# mb2.net
KiCad netlist of a schematic drawn in EAGLE
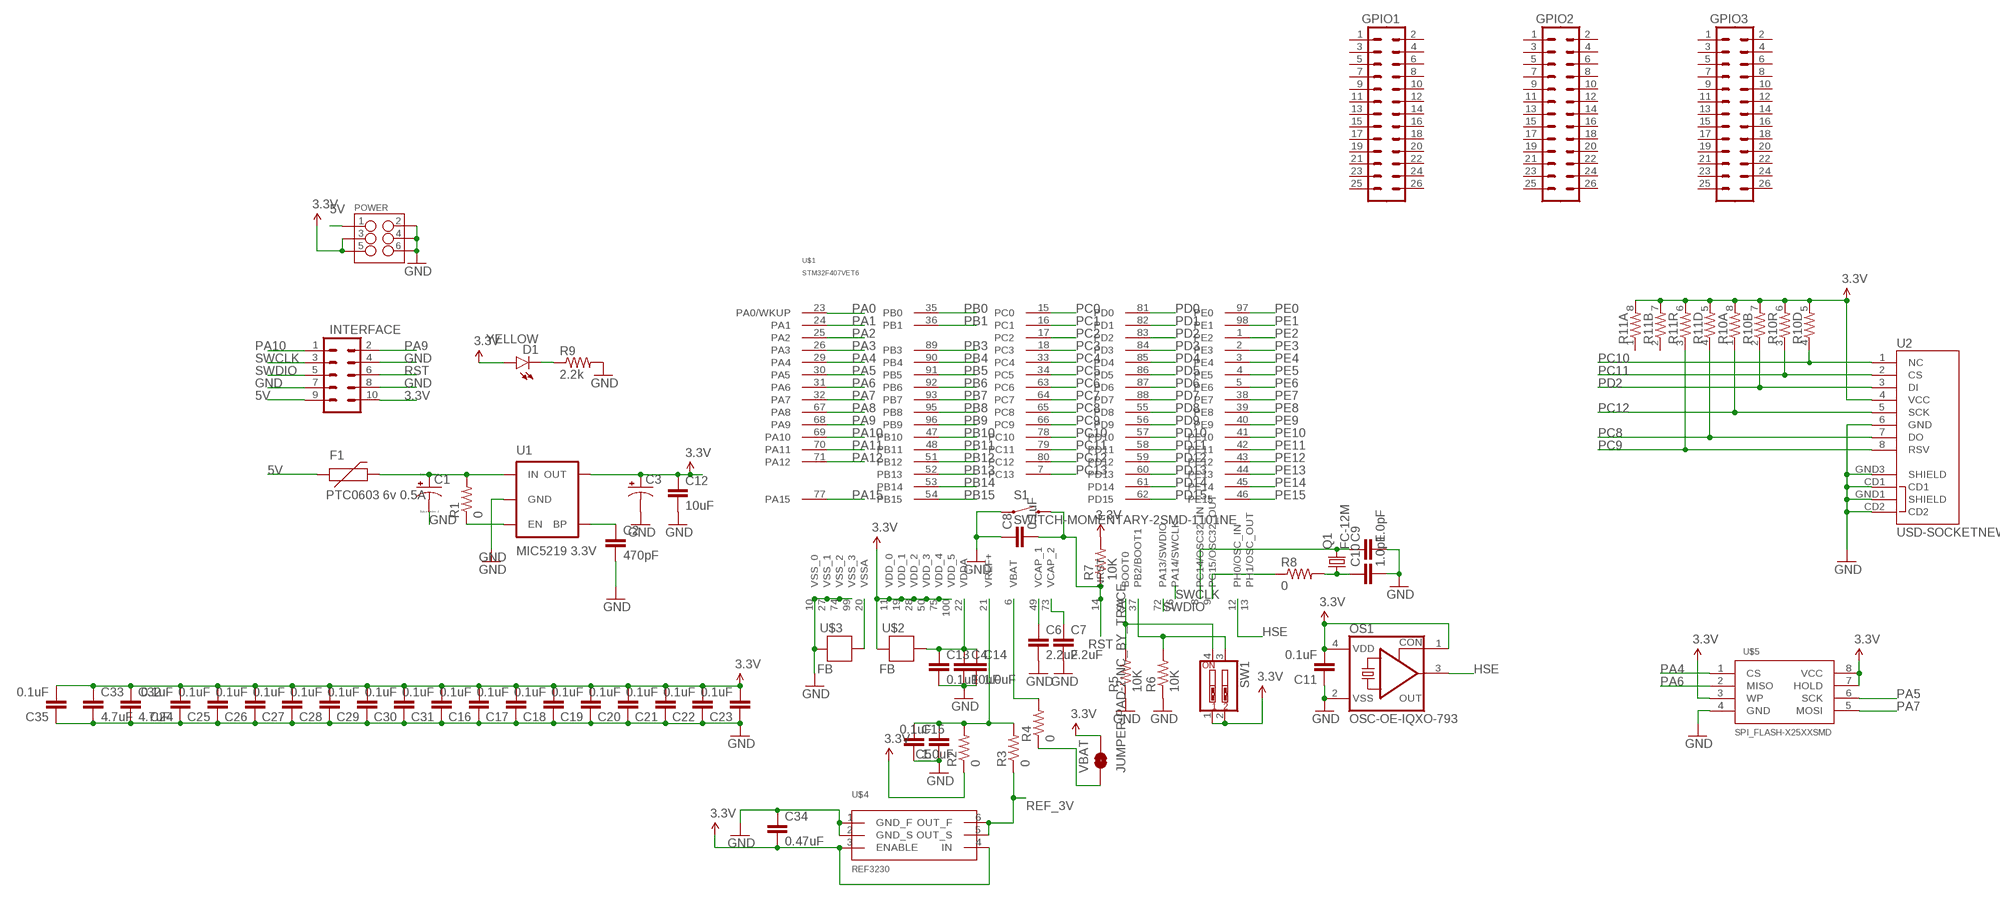
[diagram p0: schematic, sheet 1]

(export (version "E")
  (design (tool "Eeschema 10.0.6"))
  (components
    (comp (ref "C1")
      (value "CPOL-USB")
      (footprint "eagle-import:PANASONIC_B")
      (libsource (lib "eagle-import") (part "CPOL-USB"))
    )
    (comp (ref "C2")
      (value "470pF")
      (footprint "eagle-import:0603-CAP")
      (libsource (lib "eagle-import") (part "470PF-50V-5%(0603)SMD"))
    )
    (comp (ref "C3")
      (value "CAP_POL1206")
      (footprint "eagle-import:EIA3216")
      (libsource (lib "eagle-import") (part "CAP_POL1206"))
    )
    (comp (ref "C4")
      (value "10uF")
      (footprint "eagle-import:0603-CAP")
      (libsource (lib "eagle-import") (part "10UF-6.3V-20%(0603)"))
    )
    (comp (ref "C5")
      (value "0.1uF")
      (footprint "eagle-import:0603-CAP")
      (libsource (lib "eagle-import") (part "0.1UF-25V-5%(0603)"))
    )
    (comp (ref "C6")
      (value "2.2uF")
      (footprint "eagle-import:0603-CAP")
      (libsource (lib "eagle-import") (part "2.2UF-10V-20%(0603)"))
    )
    (comp (ref "C7")
      (value "2.2uF")
      (footprint "eagle-import:0603-CAP")
      (libsource (lib "eagle-import") (part "2.2UF-10V-20%(0603)"))
    )
    (comp (ref "C8")
      (value "0.1uF")
      (footprint "eagle-import:0603-CAP")
      (libsource (lib "eagle-import") (part "0.1UF-25V-5%(0603)"))
    )
    (comp (ref "C9")
      (value "1.0pF")
      (footprint "eagle-import:0603-CAP")
      (libsource (lib "eagle-import") (part "1.0PF-50V(-/+.25PF)(0603)"))
    )
    (comp (ref "C10")
      (value "1.0pF")
      (footprint "eagle-import:0603-CAP")
      (libsource (lib "eagle-import") (part "1.0PF-50V(-/+.25PF)(0603)"))
    )
    (comp (ref "C11")
      (value "0.1uF")
      (footprint "eagle-import:0603-CAP")
      (libsource (lib "eagle-import") (part "0.1UF-25V-5%(0603)"))
    )
    (comp (ref "C12")
      (value "10uF")
      (footprint "eagle-import:0603-CAP")
      (libsource (lib "eagle-import") (part "10UF-6.3V-20%(0603)"))
    )
    (comp (ref "C13")
      (value "0.1uF")
      (footprint "eagle-import:0603-CAP")
      (libsource (lib "eagle-import") (part "0.1UF-25V-5%(0603)"))
    )
    (comp (ref "C14")
      (value "1.0uF")
      (footprint "eagle-import:0603-CAP")
      (libsource (lib "eagle-import") (part "1.0UF-16V-10%(0603)"))
    )
    (comp (ref "C15")
      (value "1.0uF")
      (footprint "eagle-import:0603-CAP")
      (libsource (lib "eagle-import") (part "1.0UF-16V-10%(0603)"))
    )
    (comp (ref "C16")
      (value "0.1uF")
      (footprint "eagle-import:0603-CAP")
      (libsource (lib "eagle-import") (part "0.1UF-25V-5%(0603)"))
    )
    (comp (ref "C17")
      (value "0.1uF")
      (footprint "eagle-import:0603-CAP")
      (libsource (lib "eagle-import") (part "0.1UF-25V-5%(0603)"))
    )
    (comp (ref "C18")
      (value "0.1uF")
      (footprint "eagle-import:0603-CAP")
      (libsource (lib "eagle-import") (part "0.1UF-25V-5%(0603)"))
    )
    (comp (ref "C19")
      (value "0.1uF")
      (footprint "eagle-import:0603-CAP")
      (libsource (lib "eagle-import") (part "0.1UF-25V-5%(0603)"))
    )
    (comp (ref "C20")
      (value "0.1uF")
      (footprint "eagle-import:0603-CAP")
      (libsource (lib "eagle-import") (part "0.1UF-25V-5%(0603)"))
    )
    (comp (ref "C21")
      (value "0.1uF")
      (footprint "eagle-import:0603-CAP")
      (libsource (lib "eagle-import") (part "0.1UF-25V-5%(0603)"))
    )
    (comp (ref "C22")
      (value "0.1uF")
      (footprint "eagle-import:0603-CAP")
      (libsource (lib "eagle-import") (part "0.1UF-25V-5%(0603)"))
    )
    (comp (ref "C23")
      (value "0.1uF")
      (footprint "eagle-import:0603-CAP")
      (libsource (lib "eagle-import") (part "0.1UF-25V-5%(0603)"))
    )
    (comp (ref "C24")
      (value "0.1uF")
      (footprint "eagle-import:0603-CAP")
      (libsource (lib "eagle-import") (part "0.1UF-25V-5%(0603)"))
    )
    (comp (ref "C25")
      (value "0.1uF")
      (footprint "eagle-import:0603-CAP")
      (libsource (lib "eagle-import") (part "0.1UF-25V-5%(0603)"))
    )
    (comp (ref "C26")
      (value "0.1uF")
      (footprint "eagle-import:0603-CAP")
      (libsource (lib "eagle-import") (part "0.1UF-25V-5%(0603)"))
    )
    (comp (ref "C27")
      (value "0.1uF")
      (footprint "eagle-import:0603-CAP")
      (libsource (lib "eagle-import") (part "0.1UF-25V-5%(0603)"))
    )
    (comp (ref "C28")
      (value "0.1uF")
      (footprint "eagle-import:0603-CAP")
      (libsource (lib "eagle-import") (part "0.1UF-25V-5%(0603)"))
    )
    (comp (ref "C29")
      (value "0.1uF")
      (footprint "eagle-import:0603-CAP")
      (libsource (lib "eagle-import") (part "0.1UF-25V-5%(0603)"))
    )
    (comp (ref "C30")
      (value "0.1uF")
      (footprint "eagle-import:0603-CAP")
      (libsource (lib "eagle-import") (part "0.1UF-25V-5%(0603)"))
    )
    (comp (ref "C31")
      (value "0.1uF")
      (footprint "eagle-import:0603-CAP")
      (libsource (lib "eagle-import") (part "0.1UF-25V-5%(0603)"))
    )
    (comp (ref "C32")
      (value "4.7uF")
      (footprint "eagle-import:0603-CAP")
      (libsource (lib "eagle-import") (part "4.7UF-6.3V-10%(0603)0603"))
    )
    (comp (ref "C33")
      (value "4.7uF")
      (footprint "eagle-import:0603-CAP")
      (libsource (lib "eagle-import") (part "4.7UF-6.3V-10%(0603)0603"))
    )
    (comp (ref "C34")
      (value "0.47uF")
      (footprint "eagle-import:0603-CAP")
      (libsource (lib "eagle-import") (part "0.1UF-25V-5%(0603)"))
    )
    (comp (ref "C35")
      (value "0.1uF")
      (footprint "eagle-import:0603-CAP")
      (libsource (lib "eagle-import") (part "0.1UF-25V-5%(0603)"))
    )
    (comp (ref "D1")
      (value "YELLOW")
      (footprint "eagle-import:LED-1206")
      (libsource (lib "eagle-import") (part "LED-YELLOW1206"))
    )
    (comp (ref "F1")
      (value "PTC0603 6v 0.5A")
      (footprint "eagle-import:0603")
      (libsource (lib "eagle-import") (part "PTC0603"))
    )
    (comp (ref "GPIO1")
      (value "M13X22X13")
      (footprint "eagle-import:2X13")
      (libsource (lib "eagle-import") (part "M13X22X13"))
    )
    (comp (ref "GPIO2")
      (value "M13X22X13")
      (footprint "eagle-import:2X13")
      (libsource (lib "eagle-import") (part "M13X22X13"))
    )
    (comp (ref "GPIO3")
      (value "M13X22X13")
      (footprint "eagle-import:2X13")
      (libsource (lib "eagle-import") (part "M13X22X13"))
    )
    (comp (ref "INTERFACE")
      (value "M05X2RA")
      (footprint "eagle-import:2X5-RA")
      (libsource (lib "eagle-import") (part "M05X2RA"))
    )
    (comp (ref "OS1")
      (value "OSC-OE-IQXO-793")
      (footprint "eagle-import:2.5X2-4-PAD")
      (libsource (lib "eagle-import") (part "OSC-OE-IQXO-793"))
    )
    (comp (ref "POWER")
      (value "M03X22X3_SILK_MALE_PTH")
      (footprint "eagle-import:2X3")
      (libsource (lib "eagle-import") (part "M03X22X3_SILK_MALE_PTH"))
    )
    (comp (ref "Q1")
      (value "FC-12M")
      (footprint "eagle-import:FC-12M")
      (libsource (lib "eagle-import") (part "FC-12M"))
    )
    (comp (ref "R1")
      (value "0")
      (footprint "eagle-import:0603")
      (libsource (lib "eagle-import") (part "0OHM-1/10W-5%(0603)"))
    )
    (comp (ref "R2")
      (value "0")
      (footprint "eagle-import:0603")
      (libsource (lib "eagle-import") (part "0OHM-1/10W-5%(0603)"))
    )
    (comp (ref "R3")
      (value "0")
      (footprint "eagle-import:0603")
      (libsource (lib "eagle-import") (part "0OHM-1/10W-5%(0603)"))
    )
    (comp (ref "R4")
      (value "0")
      (footprint "eagle-import:0603")
      (libsource (lib "eagle-import") (part "0OHM-1/10W-5%(0603)"))
    )
    (comp (ref "R5")
      (value "10K")
      (footprint "eagle-import:0603-RES")
      (libsource (lib "eagle-import") (part "10KOHM-1/10W-1%(0603)0603"))
    )
    (comp (ref "R6")
      (value "10K")
      (footprint "eagle-import:0603-RES")
      (libsource (lib "eagle-import") (part "10KOHM-1/10W-1%(0603)0603"))
    )
    (comp (ref "R7")
      (value "10K")
      (footprint "eagle-import:0603-RES")
      (libsource (lib "eagle-import") (part "10KOHM-1/10W-1%(0603)0603"))
    )
    (comp (ref "R8")
      (value "0")
      (footprint "eagle-import:0603")
      (libsource (lib "eagle-import") (part "0OHM-1/10W-5%(0603)"))
    )
    (comp (ref "R9")
      (value "2.2k")
      (footprint "eagle-import:0603-RES")
      (libsource (lib "eagle-import") (part "2.2KOHM-1/10W-1%(0603)"))
    )
    (comp (ref "R10")
      (value "RESISTOR-ARRAY0603-ARV")
      (footprint "eagle-import:0603-ARV")
      (libsource (lib "eagle-import") (part "RESISTOR-ARRAY0603-ARV"))
    )
    (comp (ref "R11")
      (value "RESISTOR-ARRAY0603-ARV")
      (footprint "eagle-import:0603-ARV")
      (libsource (lib "eagle-import") (part "RESISTOR-ARRAY0603-ARV"))
    )
    (comp (ref "S1")
      (value "SWITCH-MOMENTARY-2SMD-1101NE")
      (footprint "eagle-import:TACTILE-SWITCH-1101NE")
      (libsource (lib "eagle-import") (part "SWITCH-MOMENTARY-2SMD-1101NE"))
    )
    (comp (ref "SW1")
      (value "SW_DIP-2-SMT-HALFSIZE")
      (footprint "eagle-import:DIPSWITCH-02-50MIL")
      (libsource (lib "eagle-import") (part "SW_DIP-2-SMT-HALFSIZE"))
    )
    (comp (ref "U$1")
      (value "STM32F407VET6")
      (footprint "eagle-import:LQFP-100")
      (libsource (lib "eagle-import") (part "STM32F407VET6"))
    )
    (comp (ref "U$2")
      (value "FB")
      (footprint "eagle-import:0603")
      (libsource (lib "eagle-import") (part "FB"))
    )
    (comp (ref "U$3")
      (value "FB")
      (footprint "eagle-import:0603")
      (libsource (lib "eagle-import") (part "FB"))
    )
    (comp (ref "U$4")
      (value "REF3230")
      (footprint "eagle-import:SOT23-6")
      (libsource (lib "eagle-import") (part "REF3230"))
    )
    (comp (ref "U$5")
      (value "SPI_FLASH-X25XXSMD")
      (footprint "eagle-import:SO08")
      (libsource (lib "eagle-import") (part "SPI_FLASH-X25XXSMD"))
    )
    (comp (ref "U1")
      (value "MIC5219 3.3V")
      (footprint "eagle-import:SOT23-5")
      (libsource (lib "eagle-import") (part "V_REG_MIC52193.3V"))
    )
    (comp (ref "U2")
      (value "USD-SOCKETNEW")
      (footprint "eagle-import:MICRO-SD-SOCKET-PP")
      (libsource (lib "eagle-import") (part "USD-SOCKETNEW"))
    )
    (comp (ref "VBAT")
      (value "JUMPER-PAD-2-NC_BY_TRACE")
      (footprint "eagle-import:PAD-JUMPER-2-NC_BY_TRACE_YES_SILK")
      (libsource (lib "eagle-import") (part "JUMPER-PAD-2-NC_BY_TRACE"))
    )
  )
  (nets
    (net (code "1") (name "/5V") (class "Default")
      (node (ref "F1") (pin "1") (pinfunction "1_1") (pintype "bidirectional"))
      (node (ref "INTERFACE") (pin "9") (pinfunction "9_9") (pintype "passive"))
      (node (ref "POWER") (pin "1") (pinfunction "1_1") (pintype "bidirectional"))
    )
    (net (code "2") (name "/HSE") (class "Default")
      (node (ref "OS1") (pin "3") (pinfunction "OUT_3") (pintype "output"))
      (node (ref "U$1") (pin "12") (pinfunction "PH0/OSC_IN_12") (pintype "bidirectional"))
    )
    (net (code "3") (name "/PA0") (class "Default")
      (node (ref "U$1") (pin "23") (pinfunction "PA0/WKUP_23") (pintype "bidirectional"))
    )
    (net (code "4") (name "/PA1") (class "Default")
      (node (ref "U$1") (pin "24") (pinfunction "PA1_24") (pintype "bidirectional"))
    )
    (net (code "5") (name "/PA2") (class "Default")
      (node (ref "U$1") (pin "25") (pinfunction "PA2_25") (pintype "bidirectional"))
    )
    (net (code "6") (name "/PA3") (class "Default")
      (node (ref "U$1") (pin "26") (pinfunction "PA3_26") (pintype "bidirectional"))
    )
    (net (code "7") (name "/PA4") (class "Default")
      (node (ref "U$1") (pin "29") (pinfunction "PA4_29") (pintype "bidirectional"))
      (node (ref "U$5") (pin "1") (pinfunction "CS_1") (pintype "bidirectional"))
    )
    (net (code "8") (name "/PA5") (class "Default")
      (node (ref "U$1") (pin "30") (pinfunction "PA5_30") (pintype "bidirectional"))
      (node (ref "U$5") (pin "6") (pinfunction "SCK_6") (pintype "bidirectional"))
    )
    (net (code "9") (name "/PA6") (class "Default")
      (node (ref "U$1") (pin "31") (pinfunction "PA6_31") (pintype "bidirectional"))
      (node (ref "U$5") (pin "2") (pinfunction "MISO_2") (pintype "bidirectional"))
    )
    (net (code "10") (name "/PA7") (class "Default")
      (node (ref "U$1") (pin "32") (pinfunction "PA7_32") (pintype "bidirectional"))
      (node (ref "U$5") (pin "5") (pinfunction "MOSI_5") (pintype "bidirectional"))
    )
    (net (code "11") (name "/PA8") (class "Default")
      (node (ref "U$1") (pin "67") (pinfunction "PA8_67") (pintype "bidirectional"))
    )
    (net (code "12") (name "/PA9") (class "Default")
      (node (ref "INTERFACE") (pin "2") (pinfunction "2_2") (pintype "passive"))
      (node (ref "U$1") (pin "68") (pinfunction "PA9_68") (pintype "bidirectional"))
    )
    (net (code "13") (name "/PA10") (class "Default")
      (node (ref "INTERFACE") (pin "1") (pinfunction "1_1") (pintype "passive"))
      (node (ref "U$1") (pin "69") (pinfunction "PA10_69") (pintype "bidirectional"))
    )
    (net (code "14") (name "/PA11") (class "Default")
      (node (ref "U$1") (pin "70") (pinfunction "PA11_70") (pintype "bidirectional"))
    )
    (net (code "15") (name "/PA12") (class "Default")
      (node (ref "U$1") (pin "71") (pinfunction "PA12_71") (pintype "bidirectional"))
    )
    (net (code "16") (name "/PA15") (class "Default")
      (node (ref "U$1") (pin "77") (pinfunction "PA15_77") (pintype "bidirectional"))
    )
    (net (code "17") (name "/PB0") (class "Default")
      (node (ref "U$1") (pin "35") (pinfunction "PB0_35") (pintype "bidirectional"))
    )
    (net (code "18") (name "/PB1") (class "Default")
      (node (ref "U$1") (pin "36") (pinfunction "PB1_36") (pintype "bidirectional"))
    )
    (net (code "19") (name "/PB3") (class "Default")
      (node (ref "U$1") (pin "89") (pinfunction "PB3_89") (pintype "bidirectional"))
    )
    (net (code "20") (name "/PB4") (class "Default")
      (node (ref "U$1") (pin "90") (pinfunction "PB4_90") (pintype "bidirectional"))
    )
    (net (code "21") (name "/PB5") (class "Default")
      (node (ref "U$1") (pin "91") (pinfunction "PB5_91") (pintype "bidirectional"))
    )
    (net (code "22") (name "/PB6") (class "Default")
      (node (ref "U$1") (pin "92") (pinfunction "PB6_92") (pintype "bidirectional"))
    )
    (net (code "23") (name "/PB7") (class "Default")
      (node (ref "U$1") (pin "93") (pinfunction "PB7_93") (pintype "bidirectional"))
    )
    (net (code "24") (name "/PB8") (class "Default")
      (node (ref "U$1") (pin "95") (pinfunction "PB8_95") (pintype "bidirectional"))
    )
    (net (code "25") (name "/PB9") (class "Default")
      (node (ref "U$1") (pin "96") (pinfunction "PB9_96") (pintype "bidirectional"))
    )
    (net (code "26") (name "/PB10") (class "Default")
      (node (ref "U$1") (pin "47") (pinfunction "PB10_47") (pintype "bidirectional"))
    )
    (net (code "27") (name "/PB11") (class "Default")
      (node (ref "U$1") (pin "48") (pinfunction "PB11_48") (pintype "bidirectional"))
    )
    (net (code "28") (name "/PB12") (class "Default")
      (node (ref "U$1") (pin "51") (pinfunction "PB12_51") (pintype "bidirectional"))
    )
    (net (code "29") (name "/PB13") (class "Default")
      (node (ref "U$1") (pin "52") (pinfunction "PB13_52") (pintype "bidirectional"))
    )
    (net (code "30") (name "/PB14") (class "Default")
      (node (ref "U$1") (pin "53") (pinfunction "PB14_53") (pintype "bidirectional"))
    )
    (net (code "31") (name "/PB15") (class "Default")
      (node (ref "U$1") (pin "54") (pinfunction "PB15_54") (pintype "bidirectional"))
    )
    (net (code "32") (name "/PC0") (class "Default")
      (node (ref "U$1") (pin "15") (pinfunction "PC0_15") (pintype "bidirectional"))
    )
    (net (code "33") (name "/PC1") (class "Default")
      (node (ref "U$1") (pin "16") (pinfunction "PC1_16") (pintype "bidirectional"))
    )
    (net (code "34") (name "/PC2") (class "Default")
      (node (ref "U$1") (pin "17") (pinfunction "PC2_17") (pintype "bidirectional"))
    )
    (net (code "35") (name "/PC3") (class "Default")
      (node (ref "U$1") (pin "18") (pinfunction "PC3_18") (pintype "bidirectional"))
    )
    (net (code "36") (name "/PC4") (class "Default")
      (node (ref "U$1") (pin "33") (pinfunction "PC4_33") (pintype "bidirectional"))
    )
    (net (code "37") (name "/PC5") (class "Default")
      (node (ref "U$1") (pin "34") (pinfunction "PC5_34") (pintype "bidirectional"))
    )
    (net (code "38") (name "/PC6") (class "Default")
      (node (ref "U$1") (pin "63") (pinfunction "PC6_63") (pintype "bidirectional"))
    )
    (net (code "39") (name "/PC7") (class "Default")
      (node (ref "U$1") (pin "64") (pinfunction "PC7_64") (pintype "bidirectional"))
    )
    (net (code "40") (name "/PC8") (class "Default")
      (node (ref "R11") (pin "4") (pinfunction "1_4") (pintype "passive"))
      (node (ref "U$1") (pin "65") (pinfunction "PC8_65") (pintype "bidirectional"))
      (node (ref "U2") (pin "7") (pinfunction "DO_7") (pintype "bidirectional"))
    )
    (net (code "41") (name "/PC9") (class "Default")
      (node (ref "R11") (pin "3") (pinfunction "1_3") (pintype "passive"))
      (node (ref "U$1") (pin "66") (pinfunction "PC9_66") (pintype "bidirectional"))
      (node (ref "U2") (pin "8") (pinfunction "RSV_8") (pintype "bidirectional"))
    )
    (net (code "42") (name "/PC10") (class "Default")
      (node (ref "R10") (pin "4") (pinfunction "1_4") (pintype "passive"))
      (node (ref "U$1") (pin "78") (pinfunction "PC10_78") (pintype "bidirectional"))
      (node (ref "U2") (pin "1") (pinfunction "NC_1") (pintype "bidirectional"))
    )
    (net (code "43") (name "/PC11") (class "Default")
      (node (ref "R10") (pin "3") (pinfunction "1_3") (pintype "passive"))
      (node (ref "U$1") (pin "79") (pinfunction "PC11_79") (pintype "bidirectional"))
      (node (ref "U2") (pin "2") (pinfunction "CS_2") (pintype "bidirectional"))
    )
    (net (code "44") (name "/PC12") (class "Default")
      (node (ref "R10") (pin "1") (pinfunction "1_1") (pintype "passive"))
      (node (ref "U$1") (pin "80") (pinfunction "PC12_80") (pintype "bidirectional"))
      (node (ref "U2") (pin "5") (pinfunction "SCK_5") (pintype "bidirectional"))
    )
    (net (code "45") (name "/PC13") (class "Default")
      (node (ref "U$1") (pin "7") (pinfunction "PC13_7") (pintype "bidirectional"))
    )
    (net (code "46") (name "/PD0") (class "Default")
      (node (ref "U$1") (pin "81") (pinfunction "PD0_81") (pintype "bidirectional"))
    )
    (net (code "47") (name "/PD1") (class "Default")
      (node (ref "U$1") (pin "82") (pinfunction "PD1_82") (pintype "bidirectional"))
    )
    (net (code "48") (name "/PD2") (class "Default")
      (node (ref "R10") (pin "2") (pinfunction "1_2") (pintype "passive"))
      (node (ref "U$1") (pin "83") (pinfunction "PD2_83") (pintype "bidirectional"))
      (node (ref "U2") (pin "3") (pinfunction "DI_3") (pintype "bidirectional"))
    )
    (net (code "49") (name "/PD3") (class "Default")
      (node (ref "U$1") (pin "84") (pinfunction "PD3_84") (pintype "bidirectional"))
    )
    (net (code "50") (name "/PD4") (class "Default")
      (node (ref "U$1") (pin "85") (pinfunction "PD4_85") (pintype "bidirectional"))
    )
    (net (code "51") (name "/PD5") (class "Default")
      (node (ref "U$1") (pin "86") (pinfunction "PD5_86") (pintype "bidirectional"))
    )
    (net (code "52") (name "/PD6") (class "Default")
      (node (ref "U$1") (pin "87") (pinfunction "PD6_87") (pintype "bidirectional"))
    )
    (net (code "53") (name "/PD7") (class "Default")
      (node (ref "U$1") (pin "88") (pinfunction "PD7_88") (pintype "bidirectional"))
    )
    (net (code "54") (name "/PD8") (class "Default")
      (node (ref "U$1") (pin "55") (pinfunction "PD8_55") (pintype "bidirectional"))
    )
    (net (code "55") (name "/PD9") (class "Default")
      (node (ref "U$1") (pin "56") (pinfunction "PD9_56") (pintype "bidirectional"))
    )
    (net (code "56") (name "/PD10") (class "Default")
      (node (ref "U$1") (pin "57") (pinfunction "PD10_57") (pintype "bidirectional"))
    )
    (net (code "57") (name "/PD11") (class "Default")
      (node (ref "U$1") (pin "58") (pinfunction "PD11_58") (pintype "bidirectional"))
    )
    (net (code "58") (name "/PD12") (class "Default")
      (node (ref "U$1") (pin "59") (pinfunction "PD12_59") (pintype "bidirectional"))
    )
    (net (code "59") (name "/PD13") (class "Default")
      (node (ref "U$1") (pin "60") (pinfunction "PD13_60") (pintype "bidirectional"))
    )
    (net (code "60") (name "/PD14") (class "Default")
      (node (ref "U$1") (pin "61") (pinfunction "PD14_61") (pintype "bidirectional"))
    )
    (net (code "61") (name "/PD15") (class "Default")
      (node (ref "U$1") (pin "62") (pinfunction "PD15_62") (pintype "bidirectional"))
    )
    (net (code "62") (name "/PE0") (class "Default")
      (node (ref "U$1") (pin "97") (pinfunction "PE0_97") (pintype "bidirectional"))
    )
    (net (code "63") (name "/PE1") (class "Default")
      (node (ref "U$1") (pin "98") (pinfunction "PE1_98") (pintype "bidirectional"))
    )
    (net (code "64") (name "/PE2") (class "Default")
      (node (ref "U$1") (pin "1") (pinfunction "PE2_1") (pintype "bidirectional"))
    )
    (net (code "65") (name "/PE3") (class "Default")
      (node (ref "U$1") (pin "2") (pinfunction "PE3_2") (pintype "bidirectional"))
    )
    (net (code "66") (name "/PE4") (class "Default")
      (node (ref "U$1") (pin "3") (pinfunction "PE4_3") (pintype "bidirectional"))
    )
    (net (code "67") (name "/PE5") (class "Default")
      (node (ref "U$1") (pin "4") (pinfunction "PE5_4") (pintype "bidirectional"))
    )
    (net (code "68") (name "/PE6") (class "Default")
      (node (ref "U$1") (pin "5") (pinfunction "PE6_5") (pintype "bidirectional"))
    )
    (net (code "69") (name "/PE7") (class "Default")
      (node (ref "U$1") (pin "38") (pinfunction "PE7_38") (pintype "bidirectional"))
    )
    (net (code "70") (name "/PE8") (class "Default")
      (node (ref "U$1") (pin "39") (pinfunction "PE8_39") (pintype "bidirectional"))
    )
    (net (code "71") (name "/PE9") (class "Default")
      (node (ref "U$1") (pin "40") (pinfunction "PE9_40") (pintype "bidirectional"))
    )
    (net (code "72") (name "/PE10") (class "Default")
      (node (ref "U$1") (pin "41") (pinfunction "PE10_41") (pintype "bidirectional"))
    )
    (net (code "73") (name "/PE11") (class "Default")
      (node (ref "U$1") (pin "42") (pinfunction "PE11_42") (pintype "bidirectional"))
    )
    (net (code "74") (name "/PE12") (class "Default")
      (node (ref "U$1") (pin "43") (pinfunction "PE12_43") (pintype "bidirectional"))
    )
    (net (code "75") (name "/PE13") (class "Default")
      (node (ref "U$1") (pin "44") (pinfunction "PE13_44") (pintype "bidirectional"))
    )
    (net (code "76") (name "/PE14") (class "Default")
      (node (ref "U$1") (pin "45") (pinfunction "PE14_45") (pintype "bidirectional"))
    )
    (net (code "77") (name "/PE15") (class "Default")
      (node (ref "U$1") (pin "46") (pinfunction "PE15_46") (pintype "bidirectional"))
    )
    (net (code "78") (name "/REF_3V") (class "Default")
      (node (ref "R3") (pin "1") (pinfunction "1_1") (pintype "passive"))
      (node (ref "U$4") (pin "5") (pinfunction "OUT_S_5") (pintype "bidirectional"))
      (node (ref "U$4") (pin "6") (pinfunction "OUT_F_6") (pintype "bidirectional"))
    )
    (net (code "79") (name "/RST") (class "Default")
      (node (ref "C8") (pin "2") (pinfunction "2_2") (pintype "passive"))
      (node (ref "INTERFACE") (pin "6") (pinfunction "6_6") (pintype "passive"))
      (node (ref "R7") (pin "1") (pinfunction "1_1") (pintype "passive"))
      (node (ref "S1") (pin "2") (pinfunction "2_2") (pintype "passive"))
      (node (ref "U$1") (pin "14") (pinfunction "NRST_14") (pintype "bidirectional"))
    )
    (net (code "80") (name "/SWCLK") (class "Default")
      (node (ref "INTERFACE") (pin "3") (pinfunction "3_3") (pintype "passive"))
      (node (ref "U$1") (pin "76") (pinfunction "PA14/SWCLK_76") (pintype "bidirectional"))
    )
    (net (code "81") (name "/SWDIO") (class "Default")
      (node (ref "INTERFACE") (pin "5") (pinfunction "5_5") (pintype "passive"))
      (node (ref "U$1") (pin "72") (pinfunction "PA13/SWDIO_72") (pintype "bidirectional"))
    )
    (net (code "82") (name "3.3V") (class "Default")
      (node (ref "C11") (pin "2") (pinfunction "2_2") (pintype "passive"))
      (node (ref "C12") (pin "1") (pinfunction "1_1") (pintype "passive"))
      (node (ref "C16") (pin "2") (pinfunction "2_2") (pintype "passive"))
      (node (ref "C17") (pin "2") (pinfunction "2_2") (pintype "passive"))
      (node (ref "C18") (pin "2") (pinfunction "2_2") (pintype "passive"))
      (node (ref "C19") (pin "2") (pinfunction "2_2") (pintype "passive"))
      (node (ref "C20") (pin "2") (pinfunction "2_2") (pintype "passive"))
      (node (ref "C21") (pin "2") (pinfunction "2_2") (pintype "passive"))
      (node (ref "C22") (pin "2") (pinfunction "2_2") (pintype "passive"))
      (node (ref "C23") (pin "2") (pinfunction "2_2") (pintype "passive"))
      (node (ref "C24") (pin "2") (pinfunction "2_2") (pintype "passive"))
      (node (ref "C25") (pin "2") (pinfunction "2_2") (pintype "passive"))
      (node (ref "C26") (pin "2") (pinfunction "2_2") (pintype "passive"))
      (node (ref "C27") (pin "2") (pinfunction "2_2") (pintype "passive"))
      (node (ref "C28") (pin "2") (pinfunction "2_2") (pintype "passive"))
      (node (ref "C29") (pin "2") (pinfunction "2_2") (pintype "passive"))
      (node (ref "C3") (pin "A") (pinfunction "+_A") (pintype "passive"))
      (node (ref "C30") (pin "2") (pinfunction "2_2") (pintype "passive"))
      (node (ref "C31") (pin "2") (pinfunction "2_2") (pintype "passive"))
      (node (ref "C32") (pin "1") (pinfunction "1_1") (pintype "passive"))
      (node (ref "C33") (pin "1") (pinfunction "1_1") (pintype "passive"))
      (node (ref "C34") (pin "2") (pinfunction "2_2") (pintype "passive"))
      (node (ref "C35") (pin "2") (pinfunction "2_2") (pintype "passive"))
      (node (ref "D1") (pin "A") (pinfunction "A_A") (pintype "passive"))
      (node (ref "INTERFACE") (pin "10") (pinfunction "10_10") (pintype "passive"))
      (node (ref "OS1") (pin "1") (pinfunction "CON_1") (pintype "input"))
      (node (ref "OS1") (pin "4") (pinfunction "VDD_4") (pintype "power_in"))
      (node (ref "POWER") (pin "3") (pinfunction "3_3") (pintype "bidirectional"))
      (node (ref "POWER") (pin "5") (pinfunction "5_5") (pintype "bidirectional"))
      (node (ref "R10") (pin "5") (pinfunction "2_5") (pintype "passive"))
      (node (ref "R10") (pin "6") (pinfunction "2_6") (pintype "passive"))
      (node (ref "R10") (pin "7") (pinfunction "2_7") (pintype "passive"))
      (node (ref "R10") (pin "8") (pinfunction "2_8") (pintype "passive"))
      (node (ref "R11") (pin "5") (pinfunction "2_5") (pintype "passive"))
      (node (ref "R11") (pin "6") (pinfunction "2_6") (pintype "passive"))
      (node (ref "R11") (pin "7") (pinfunction "2_7") (pintype "passive"))
      (node (ref "R11") (pin "8") (pinfunction "2_8") (pintype "passive"))
      (node (ref "R2") (pin "1") (pinfunction "1_1") (pintype "passive"))
      (node (ref "R7") (pin "2") (pinfunction "2_2") (pintype "passive"))
      (node (ref "SW1") (pin "1") (pinfunction "1_1") (pintype "passive"))
      (node (ref "SW1") (pin "2") (pinfunction "2_2") (pintype "passive"))
      (node (ref "U$1") (pin "100") (pinfunction "VDD_5_100") (pintype "power_in"))
      (node (ref "U$1") (pin "11") (pinfunction "VDD_0_11") (pintype "power_in"))
      (node (ref "U$1") (pin "19") (pinfunction "VDD_1_19") (pintype "power_in"))
      (node (ref "U$1") (pin "28") (pinfunction "VDD_2_28") (pintype "power_in"))
      (node (ref "U$1") (pin "50") (pinfunction "VDD_3_50") (pintype "power_in"))
      (node (ref "U$1") (pin "75") (pinfunction "VDD_4_75") (pintype "power_in"))
      (node (ref "U$2") (pin "2") (pinfunction "P$2_2") (pintype "bidirectional"))
      (node (ref "U$4") (pin "3") (pinfunction "ENABLE_3") (pintype "bidirectional"))
      (node (ref "U$4") (pin "4") (pinfunction "IN_4") (pintype "bidirectional"))
      (node (ref "U$5") (pin "3") (pinfunction "WP_3") (pintype "bidirectional"))
      (node (ref "U$5") (pin "7") (pinfunction "HOLD_7") (pintype "bidirectional"))
      (node (ref "U$5") (pin "8") (pinfunction "VCC_8") (pintype "bidirectional"))
      (node (ref "U1") (pin "5") (pinfunction "OUT_5") (pintype "passive"))
      (node (ref "U2") (pin "4") (pinfunction "VCC_4") (pintype "bidirectional"))
      (node (ref "VBAT") (pin "2") (pinfunction "2_2") (pintype "passive"))
    )
    (net (code "83") (name "GND") (class "Default")
      (node (ref "C1") (pin "-") (pinfunction "-_-") (pintype "passive"))
      (node (ref "C10") (pin "2") (pinfunction "2_2") (pintype "passive"))
      (node (ref "C11") (pin "1") (pinfunction "1_1") (pintype "passive"))
      (node (ref "C12") (pin "2") (pinfunction "2_2") (pintype "passive"))
      (node (ref "C13") (pin "2") (pinfunction "2_2") (pintype "passive"))
      (node (ref "C14") (pin "2") (pinfunction "2_2") (pintype "passive"))
      (node (ref "C15") (pin "2") (pinfunction "2_2") (pintype "passive"))
      (node (ref "C16") (pin "1") (pinfunction "1_1") (pintype "passive"))
      (node (ref "C17") (pin "1") (pinfunction "1_1") (pintype "passive"))
      (node (ref "C18") (pin "1") (pinfunction "1_1") (pintype "passive"))
      (node (ref "C19") (pin "1") (pinfunction "1_1") (pintype "passive"))
      (node (ref "C2") (pin "2") (pinfunction "2_2") (pintype "passive"))
      (node (ref "C20") (pin "1") (pinfunction "1_1") (pintype "passive"))
      (node (ref "C21") (pin "1") (pinfunction "1_1") (pintype "passive"))
      (node (ref "C22") (pin "1") (pinfunction "1_1") (pintype "passive"))
      (node (ref "C23") (pin "1") (pinfunction "1_1") (pintype "passive"))
      (node (ref "C24") (pin "1") (pinfunction "1_1") (pintype "passive"))
      (node (ref "C25") (pin "1") (pinfunction "1_1") (pintype "passive"))
      (node (ref "C26") (pin "1") (pinfunction "1_1") (pintype "passive"))
      (node (ref "C27") (pin "1") (pinfunction "1_1") (pintype "passive"))
      (node (ref "C28") (pin "1") (pinfunction "1_1") (pintype "passive"))
      (node (ref "C29") (pin "1") (pinfunction "1_1") (pintype "passive"))
      (node (ref "C3") (pin "C") (pinfunction "-_C") (pintype "passive"))
      (node (ref "C30") (pin "1") (pinfunction "1_1") (pintype "passive"))
      (node (ref "C31") (pin "1") (pinfunction "1_1") (pintype "passive"))
      (node (ref "C32") (pin "2") (pinfunction "2_2") (pintype "passive"))
      (node (ref "C33") (pin "2") (pinfunction "2_2") (pintype "passive"))
      (node (ref "C34") (pin "1") (pinfunction "1_1") (pintype "passive"))
      (node (ref "C35") (pin "1") (pinfunction "1_1") (pintype "passive"))
      (node (ref "C4") (pin "2") (pinfunction "2_2") (pintype "passive"))
      (node (ref "C5") (pin "1") (pinfunction "1_1") (pintype "passive"))
      (node (ref "C6") (pin "2") (pinfunction "2_2") (pintype "passive"))
      (node (ref "C7") (pin "2") (pinfunction "2_2") (pintype "passive"))
      (node (ref "C8") (pin "1") (pinfunction "1_1") (pintype "passive"))
      (node (ref "C9") (pin "2") (pinfunction "2_2") (pintype "passive"))
      (node (ref "INTERFACE") (pin "4") (pinfunction "4_4") (pintype "passive"))
      (node (ref "INTERFACE") (pin "7") (pinfunction "7_7") (pintype "passive"))
      (node (ref "INTERFACE") (pin "8") (pinfunction "8_8") (pintype "passive"))
      (node (ref "OS1") (pin "2") (pinfunction "VSS_2") (pintype "power_in"))
      (node (ref "POWER") (pin "2") (pinfunction "2_2") (pintype "bidirectional"))
      (node (ref "POWER") (pin "4") (pinfunction "4_4") (pintype "bidirectional"))
      (node (ref "POWER") (pin "6") (pinfunction "6_6") (pintype "bidirectional"))
      (node (ref "R5") (pin "1") (pinfunction "1_1") (pintype "passive"))
      (node (ref "R6") (pin "1") (pinfunction "1_1") (pintype "passive"))
      (node (ref "R9") (pin "2") (pinfunction "2_2") (pintype "passive"))
      (node (ref "S1") (pin "1") (pinfunction "1_1") (pintype "passive"))
      (node (ref "U$1") (pin "10") (pinfunction "VSS_0_10") (pintype "power_in"))
      (node (ref "U$1") (pin "27") (pinfunction "VSS_1_27") (pintype "power_in"))
      (node (ref "U$1") (pin "74") (pinfunction "VSS_2_74") (pintype "power_in"))
      (node (ref "U$1") (pin "99") (pinfunction "VSS_3_99") (pintype "power_in"))
      (node (ref "U$3") (pin "2") (pinfunction "P$2_2") (pintype "bidirectional"))
      (node (ref "U$4") (pin "1") (pinfunction "GND_F_1") (pintype "bidirectional"))
      (node (ref "U$4") (pin "2") (pinfunction "GND_S_2") (pintype "bidirectional"))
      (node (ref "U$5") (pin "4") (pinfunction "GND_4") (pintype "bidirectional"))
      (node (ref "U1") (pin "2") (pinfunction "GND_2") (pintype "input"))
      (node (ref "U2") (pin "6") (pinfunction "GND_6") (pintype "bidirectional"))
      (node (ref "U2") (pin "CD1") (pinfunction "CD1_CD1") (pintype "bidirectional"))
      (node (ref "U2") (pin "CD2") (pinfunction "CD2_CD2") (pintype "bidirectional"))
      (node (ref "U2") (pin "GND1") (pinfunction "SHIELD_GND1") (pintype "bidirectional"))
      (node (ref "U2") (pin "GND3") (pinfunction "SHIELD_GND3") (pintype "bidirectional"))
    )
    (net (code "84") (name "Net-(C10-Pad1)") (class "Default")
      (node (ref "C10") (pin "1") (pinfunction "1_1") (pintype "passive"))
      (node (ref "Q1") (pin "1") (pinfunction "1_1") (pintype "passive"))
      (node (ref "R8") (pin "2") (pinfunction "2_2") (pintype "passive"))
    )
    (net (code "85") (name "Net-(D1-PadC)") (class "Default")
      (node (ref "D1") (pin "C") (pinfunction "C_C") (pintype "passive"))
      (node (ref "R9") (pin "1") (pinfunction "1_1") (pintype "passive"))
    )
    (net (code "86") (name "Net-(R4-Pad1)") (class "Default")
      (node (ref "R4") (pin "1") (pinfunction "1_1") (pintype "passive"))
      (node (ref "VBAT") (pin "1") (pinfunction "1_1") (pintype "passive"))
    )
    (net (code "87") (name "Net-(U$1-BOOT0)") (class "Default")
      (node (ref "R5") (pin "2") (pinfunction "2_2") (pintype "passive"))
      (node (ref "SW1") (pin "4") (pinfunction "4_4") (pintype "passive"))
      (node (ref "U$1") (pin "94") (pinfunction "BOOT0_94") (pintype "bidirectional"))
    )
    (net (code "88") (name "Net-(U$1-PB2{slash}BOOT1)") (class "Default")
      (node (ref "R6") (pin "2") (pinfunction "2_2") (pintype "passive"))
      (node (ref "SW1") (pin "3") (pinfunction "3_3") (pintype "passive"))
      (node (ref "U$1") (pin "37") (pinfunction "PB2/BOOT1_37") (pintype "bidirectional"))
    )
    (net (code "89") (name "Net-(U$1-PC14{slash}OSC32_IN)") (class "Default")
      (node (ref "C9") (pin "1") (pinfunction "1_1") (pintype "passive"))
      (node (ref "Q1") (pin "2") (pinfunction "2_2") (pintype "passive"))
      (node (ref "U$1") (pin "8") (pinfunction "PC14/OSC32_IN_8") (pintype "bidirectional"))
    )
    (net (code "90") (name "Net-(U$1-PC15{slash}OSC32_OUT)") (class "Default")
      (node (ref "R8") (pin "1") (pinfunction "1_1") (pintype "passive"))
      (node (ref "U$1") (pin "9") (pinfunction "PC15/OSC32_OUT_9") (pintype "bidirectional"))
    )
    (net (code "91") (name "Net-(U$1-VBAT)") (class "Default")
      (node (ref "R4") (pin "2") (pinfunction "2_2") (pintype "passive"))
      (node (ref "U$1") (pin "6") (pinfunction "VBAT_6") (pintype "power_in"))
    )
    (net (code "92") (name "Net-(U$1-VCAP_1)") (class "Default")
      (node (ref "C6") (pin "1") (pinfunction "1_1") (pintype "passive"))
      (node (ref "U$1") (pin "49") (pinfunction "VCAP_1_49") (pintype "bidirectional"))
    )
    (net (code "93") (name "Net-(U$1-VCAP_2)") (class "Default")
      (node (ref "C7") (pin "1") (pinfunction "1_1") (pintype "passive"))
      (node (ref "U$1") (pin "73") (pinfunction "VCAP_2_73") (pintype "bidirectional"))
    )
    (net (code "94") (name "Net-(U$1-VDDA)") (class "Default")
      (node (ref "C13") (pin "1") (pinfunction "1_1") (pintype "passive"))
      (node (ref "C14") (pin "1") (pinfunction "1_1") (pintype "passive"))
      (node (ref "C4") (pin "1") (pinfunction "1_1") (pintype "passive"))
      (node (ref "U$1") (pin "22") (pinfunction "VDDA_22") (pintype "power_in"))
      (node (ref "U$2") (pin "1") (pinfunction "P$1_1") (pintype "bidirectional"))
    )
    (net (code "95") (name "Net-(U$1-VREF+)") (class "Default")
      (node (ref "C15") (pin "1") (pinfunction "1_1") (pintype "passive"))
      (node (ref "C5") (pin "2") (pinfunction "2_2") (pintype "passive"))
      (node (ref "R2") (pin "2") (pinfunction "2_2") (pintype "passive"))
      (node (ref "R3") (pin "2") (pinfunction "2_2") (pintype "passive"))
      (node (ref "U$1") (pin "21") (pinfunction "VREF+_21") (pintype "power_in"))
    )
    (net (code "96") (name "Net-(U$1-VSSA)") (class "Default")
      (node (ref "U$1") (pin "20") (pinfunction "VSSA_20") (pintype "power_in"))
      (node (ref "U$3") (pin "1") (pinfunction "P$1_1") (pintype "bidirectional"))
    )
    (net (code "97") (name "Net-(U1-BP)") (class "Default")
      (node (ref "C2") (pin "1") (pinfunction "1_1") (pintype "passive"))
      (node (ref "U1") (pin "4") (pinfunction "BP_4") (pintype "input"))
    )
    (net (code "98") (name "Net-(U1-EN)") (class "Default")
      (node (ref "R1") (pin "1") (pinfunction "1_1") (pintype "passive"))
      (node (ref "U1") (pin "3") (pinfunction "EN_3") (pintype "input"))
    )
    (net (code "99") (name "Net-(U1-IN)") (class "Default")
      (node (ref "C1") (pin "+") (pinfunction "+_+") (pintype "passive"))
      (node (ref "F1") (pin "2") (pinfunction "2_2") (pintype "bidirectional"))
      (node (ref "R1") (pin "2") (pinfunction "2_2") (pintype "passive"))
      (node (ref "U1") (pin "1") (pinfunction "IN_1") (pintype "input"))
    )
    (net (code "100") (name "unconnected-(GPIO1-Pad1)") (class "Default")
      (node (ref "GPIO1") (pin "1") (pinfunction "1_1") (pintype "passive"))
    )
    (net (code "101") (name "unconnected-(GPIO1-Pad2)") (class "Default")
      (node (ref "GPIO1") (pin "2") (pinfunction "2_2") (pintype "passive"))
    )
    (net (code "102") (name "unconnected-(GPIO1-Pad3)") (class "Default")
      (node (ref "GPIO1") (pin "3") (pinfunction "3_3") (pintype "passive"))
    )
    (net (code "103") (name "unconnected-(GPIO1-Pad4)") (class "Default")
      (node (ref "GPIO1") (pin "4") (pinfunction "4_4") (pintype "passive"))
    )
    (net (code "104") (name "unconnected-(GPIO1-Pad5)") (class "Default")
      (node (ref "GPIO1") (pin "5") (pinfunction "5_5") (pintype "passive"))
    )
    (net (code "105") (name "unconnected-(GPIO1-Pad6)") (class "Default")
      (node (ref "GPIO1") (pin "6") (pinfunction "6_6") (pintype "passive"))
    )
    (net (code "106") (name "unconnected-(GPIO1-Pad7)") (class "Default")
      (node (ref "GPIO1") (pin "7") (pinfunction "7_7") (pintype "passive"))
    )
    (net (code "107") (name "unconnected-(GPIO1-Pad8)") (class "Default")
      (node (ref "GPIO1") (pin "8") (pinfunction "8_8") (pintype "passive"))
    )
    (net (code "108") (name "unconnected-(GPIO1-Pad9)") (class "Default")
      (node (ref "GPIO1") (pin "9") (pinfunction "9_9") (pintype "passive"))
    )
    (net (code "109") (name "unconnected-(GPIO1-Pad10)") (class "Default")
      (node (ref "GPIO1") (pin "10") (pinfunction "10_10") (pintype "passive"))
    )
    (net (code "110") (name "unconnected-(GPIO1-Pad11)") (class "Default")
      (node (ref "GPIO1") (pin "11") (pinfunction "11_11") (pintype "passive"))
    )
    (net (code "111") (name "unconnected-(GPIO1-Pad12)") (class "Default")
      (node (ref "GPIO1") (pin "12") (pinfunction "12_12") (pintype "passive"))
    )
    (net (code "112") (name "unconnected-(GPIO1-Pad13)") (class "Default")
      (node (ref "GPIO1") (pin "13") (pinfunction "13_13") (pintype "passive"))
    )
    (net (code "113") (name "unconnected-(GPIO1-Pad14)") (class "Default")
      (node (ref "GPIO1") (pin "14") (pinfunction "14_14") (pintype "passive"))
    )
    (net (code "114") (name "unconnected-(GPIO1-Pad15)") (class "Default")
      (node (ref "GPIO1") (pin "15") (pinfunction "15_15") (pintype "passive"))
    )
    (net (code "115") (name "unconnected-(GPIO1-Pad16)") (class "Default")
      (node (ref "GPIO1") (pin "16") (pinfunction "16_16") (pintype "passive"))
    )
    (net (code "116") (name "unconnected-(GPIO1-Pad17)") (class "Default")
      (node (ref "GPIO1") (pin "17") (pinfunction "17_17") (pintype "passive"))
    )
    (net (code "117") (name "unconnected-(GPIO1-Pad18)") (class "Default")
      (node (ref "GPIO1") (pin "18") (pinfunction "18_18") (pintype "passive"))
    )
    (net (code "118") (name "unconnected-(GPIO1-Pad19)") (class "Default")
      (node (ref "GPIO1") (pin "19") (pinfunction "19_19") (pintype "passive"))
    )
    (net (code "119") (name "unconnected-(GPIO1-Pad20)") (class "Default")
      (node (ref "GPIO1") (pin "20") (pinfunction "20_20") (pintype "passive"))
    )
    (net (code "120") (name "unconnected-(GPIO1-Pad21)") (class "Default")
      (node (ref "GPIO1") (pin "21") (pinfunction "21_21") (pintype "passive"))
    )
    (net (code "121") (name "unconnected-(GPIO1-Pad22)") (class "Default")
      (node (ref "GPIO1") (pin "22") (pinfunction "22_22") (pintype "passive"))
    )
    (net (code "122") (name "unconnected-(GPIO1-Pad23)") (class "Default")
      (node (ref "GPIO1") (pin "23") (pinfunction "23_23") (pintype "passive"))
    )
    (net (code "123") (name "unconnected-(GPIO1-Pad24)") (class "Default")
      (node (ref "GPIO1") (pin "24") (pinfunction "24_24") (pintype "passive"))
    )
    (net (code "124") (name "unconnected-(GPIO1-Pad25)") (class "Default")
      (node (ref "GPIO1") (pin "25") (pinfunction "25_25") (pintype "passive"))
    )
    (net (code "125") (name "unconnected-(GPIO1-Pad26)") (class "Default")
      (node (ref "GPIO1") (pin "26") (pinfunction "26_26") (pintype "passive"))
    )
    (net (code "126") (name "unconnected-(GPIO2-Pad1)") (class "Default")
      (node (ref "GPIO2") (pin "1") (pinfunction "1_1") (pintype "passive"))
    )
    (net (code "127") (name "unconnected-(GPIO2-Pad2)") (class "Default")
      (node (ref "GPIO2") (pin "2") (pinfunction "2_2") (pintype "passive"))
    )
    (net (code "128") (name "unconnected-(GPIO2-Pad3)") (class "Default")
      (node (ref "GPIO2") (pin "3") (pinfunction "3_3") (pintype "passive"))
    )
    (net (code "129") (name "unconnected-(GPIO2-Pad4)") (class "Default")
      (node (ref "GPIO2") (pin "4") (pinfunction "4_4") (pintype "passive"))
    )
    (net (code "130") (name "unconnected-(GPIO2-Pad5)") (class "Default")
      (node (ref "GPIO2") (pin "5") (pinfunction "5_5") (pintype "passive"))
    )
    (net (code "131") (name "unconnected-(GPIO2-Pad6)") (class "Default")
      (node (ref "GPIO2") (pin "6") (pinfunction "6_6") (pintype "passive"))
    )
    (net (code "132") (name "unconnected-(GPIO2-Pad7)") (class "Default")
      (node (ref "GPIO2") (pin "7") (pinfunction "7_7") (pintype "passive"))
    )
    (net (code "133") (name "unconnected-(GPIO2-Pad8)") (class "Default")
      (node (ref "GPIO2") (pin "8") (pinfunction "8_8") (pintype "passive"))
    )
    (net (code "134") (name "unconnected-(GPIO2-Pad9)") (class "Default")
      (node (ref "GPIO2") (pin "9") (pinfunction "9_9") (pintype "passive"))
    )
    (net (code "135") (name "unconnected-(GPIO2-Pad10)") (class "Default")
      (node (ref "GPIO2") (pin "10") (pinfunction "10_10") (pintype "passive"))
    )
    (net (code "136") (name "unconnected-(GPIO2-Pad11)") (class "Default")
      (node (ref "GPIO2") (pin "11") (pinfunction "11_11") (pintype "passive"))
    )
    (net (code "137") (name "unconnected-(GPIO2-Pad12)") (class "Default")
      (node (ref "GPIO2") (pin "12") (pinfunction "12_12") (pintype "passive"))
    )
    (net (code "138") (name "unconnected-(GPIO2-Pad13)") (class "Default")
      (node (ref "GPIO2") (pin "13") (pinfunction "13_13") (pintype "passive"))
    )
    (net (code "139") (name "unconnected-(GPIO2-Pad14)") (class "Default")
      (node (ref "GPIO2") (pin "14") (pinfunction "14_14") (pintype "passive"))
    )
    (net (code "140") (name "unconnected-(GPIO2-Pad15)") (class "Default")
      (node (ref "GPIO2") (pin "15") (pinfunction "15_15") (pintype "passive"))
    )
    (net (code "141") (name "unconnected-(GPIO2-Pad16)") (class "Default")
      (node (ref "GPIO2") (pin "16") (pinfunction "16_16") (pintype "passive"))
    )
    (net (code "142") (name "unconnected-(GPIO2-Pad17)") (class "Default")
      (node (ref "GPIO2") (pin "17") (pinfunction "17_17") (pintype "passive"))
    )
    (net (code "143") (name "unconnected-(GPIO2-Pad18)") (class "Default")
      (node (ref "GPIO2") (pin "18") (pinfunction "18_18") (pintype "passive"))
    )
    (net (code "144") (name "unconnected-(GPIO2-Pad19)") (class "Default")
      (node (ref "GPIO2") (pin "19") (pinfunction "19_19") (pintype "passive"))
    )
    (net (code "145") (name "unconnected-(GPIO2-Pad20)") (class "Default")
      (node (ref "GPIO2") (pin "20") (pinfunction "20_20") (pintype "passive"))
    )
    (net (code "146") (name "unconnected-(GPIO2-Pad21)") (class "Default")
      (node (ref "GPIO2") (pin "21") (pinfunction "21_21") (pintype "passive"))
    )
    (net (code "147") (name "unconnected-(GPIO2-Pad22)") (class "Default")
      (node (ref "GPIO2") (pin "22") (pinfunction "22_22") (pintype "passive"))
    )
    (net (code "148") (name "unconnected-(GPIO2-Pad23)") (class "Default")
      (node (ref "GPIO2") (pin "23") (pinfunction "23_23") (pintype "passive"))
    )
    (net (code "149") (name "unconnected-(GPIO2-Pad24)") (class "Default")
      (node (ref "GPIO2") (pin "24") (pinfunction "24_24") (pintype "passive"))
    )
    (net (code "150") (name "unconnected-(GPIO2-Pad25)") (class "Default")
      (node (ref "GPIO2") (pin "25") (pinfunction "25_25") (pintype "passive"))
    )
    (net (code "151") (name "unconnected-(GPIO2-Pad26)") (class "Default")
      (node (ref "GPIO2") (pin "26") (pinfunction "26_26") (pintype "passive"))
    )
    (net (code "152") (name "unconnected-(GPIO3-Pad1)") (class "Default")
      (node (ref "GPIO3") (pin "1") (pinfunction "1_1") (pintype "passive"))
    )
    (net (code "153") (name "unconnected-(GPIO3-Pad2)") (class "Default")
      (node (ref "GPIO3") (pin "2") (pinfunction "2_2") (pintype "passive"))
    )
    (net (code "154") (name "unconnected-(GPIO3-Pad3)") (class "Default")
      (node (ref "GPIO3") (pin "3") (pinfunction "3_3") (pintype "passive"))
    )
    (net (code "155") (name "unconnected-(GPIO3-Pad4)") (class "Default")
      (node (ref "GPIO3") (pin "4") (pinfunction "4_4") (pintype "passive"))
    )
    (net (code "156") (name "unconnected-(GPIO3-Pad5)") (class "Default")
      (node (ref "GPIO3") (pin "5") (pinfunction "5_5") (pintype "passive"))
    )
    (net (code "157") (name "unconnected-(GPIO3-Pad6)") (class "Default")
      (node (ref "GPIO3") (pin "6") (pinfunction "6_6") (pintype "passive"))
    )
    (net (code "158") (name "unconnected-(GPIO3-Pad7)") (class "Default")
      (node (ref "GPIO3") (pin "7") (pinfunction "7_7") (pintype "passive"))
    )
    (net (code "159") (name "unconnected-(GPIO3-Pad8)") (class "Default")
      (node (ref "GPIO3") (pin "8") (pinfunction "8_8") (pintype "passive"))
    )
    (net (code "160") (name "unconnected-(GPIO3-Pad9)") (class "Default")
      (node (ref "GPIO3") (pin "9") (pinfunction "9_9") (pintype "passive"))
    )
    (net (code "161") (name "unconnected-(GPIO3-Pad10)") (class "Default")
      (node (ref "GPIO3") (pin "10") (pinfunction "10_10") (pintype "passive"))
    )
    (net (code "162") (name "unconnected-(GPIO3-Pad11)") (class "Default")
      (node (ref "GPIO3") (pin "11") (pinfunction "11_11") (pintype "passive"))
    )
    (net (code "163") (name "unconnected-(GPIO3-Pad12)") (class "Default")
      (node (ref "GPIO3") (pin "12") (pinfunction "12_12") (pintype "passive"))
    )
    (net (code "164") (name "unconnected-(GPIO3-Pad13)") (class "Default")
      (node (ref "GPIO3") (pin "13") (pinfunction "13_13") (pintype "passive"))
    )
    (net (code "165") (name "unconnected-(GPIO3-Pad14)") (class "Default")
      (node (ref "GPIO3") (pin "14") (pinfunction "14_14") (pintype "passive"))
    )
    (net (code "166") (name "unconnected-(GPIO3-Pad15)") (class "Default")
      (node (ref "GPIO3") (pin "15") (pinfunction "15_15") (pintype "passive"))
    )
    (net (code "167") (name "unconnected-(GPIO3-Pad16)") (class "Default")
      (node (ref "GPIO3") (pin "16") (pinfunction "16_16") (pintype "passive"))
    )
    (net (code "168") (name "unconnected-(GPIO3-Pad17)") (class "Default")
      (node (ref "GPIO3") (pin "17") (pinfunction "17_17") (pintype "passive"))
    )
    (net (code "169") (name "unconnected-(GPIO3-Pad18)") (class "Default")
      (node (ref "GPIO3") (pin "18") (pinfunction "18_18") (pintype "passive"))
    )
    (net (code "170") (name "unconnected-(GPIO3-Pad19)") (class "Default")
      (node (ref "GPIO3") (pin "19") (pinfunction "19_19") (pintype "passive"))
    )
    (net (code "171") (name "unconnected-(GPIO3-Pad20)") (class "Default")
      (node (ref "GPIO3") (pin "20") (pinfunction "20_20") (pintype "passive"))
    )
    (net (code "172") (name "unconnected-(GPIO3-Pad21)") (class "Default")
      (node (ref "GPIO3") (pin "21") (pinfunction "21_21") (pintype "passive"))
    )
    (net (code "173") (name "unconnected-(GPIO3-Pad22)") (class "Default")
      (node (ref "GPIO3") (pin "22") (pinfunction "22_22") (pintype "passive"))
    )
    (net (code "174") (name "unconnected-(GPIO3-Pad23)") (class "Default")
      (node (ref "GPIO3") (pin "23") (pinfunction "23_23") (pintype "passive"))
    )
    (net (code "175") (name "unconnected-(GPIO3-Pad24)") (class "Default")
      (node (ref "GPIO3") (pin "24") (pinfunction "24_24") (pintype "passive"))
    )
    (net (code "176") (name "unconnected-(GPIO3-Pad25)") (class "Default")
      (node (ref "GPIO3") (pin "25") (pinfunction "25_25") (pintype "passive"))
    )
    (net (code "177") (name "unconnected-(GPIO3-Pad26)") (class "Default")
      (node (ref "GPIO3") (pin "26") (pinfunction "26_26") (pintype "passive"))
    )
    (net (code "178") (name "unconnected-(R11-Pad1)") (class "Default")
      (node (ref "R11") (pin "1") (pinfunction "1_1") (pintype "passive"))
    )
    (net (code "179") (name "unconnected-(R11B-1-Pad2)") (class "Default")
      (node (ref "R11") (pin "2") (pinfunction "1_2") (pintype "passive"))
    )
    (net (code "180") (name "unconnected-(U$1-PH1{slash}OSC_OUT-Pad13)") (class "Default")
      (node (ref "U$1") (pin "13") (pinfunction "PH1/OSC_OUT_13") (pintype "bidirectional"))
    )
  )
)
